# SparkFun_Teensy_Adapter.net
KiCad netlist of a schematic drawn in EAGLE
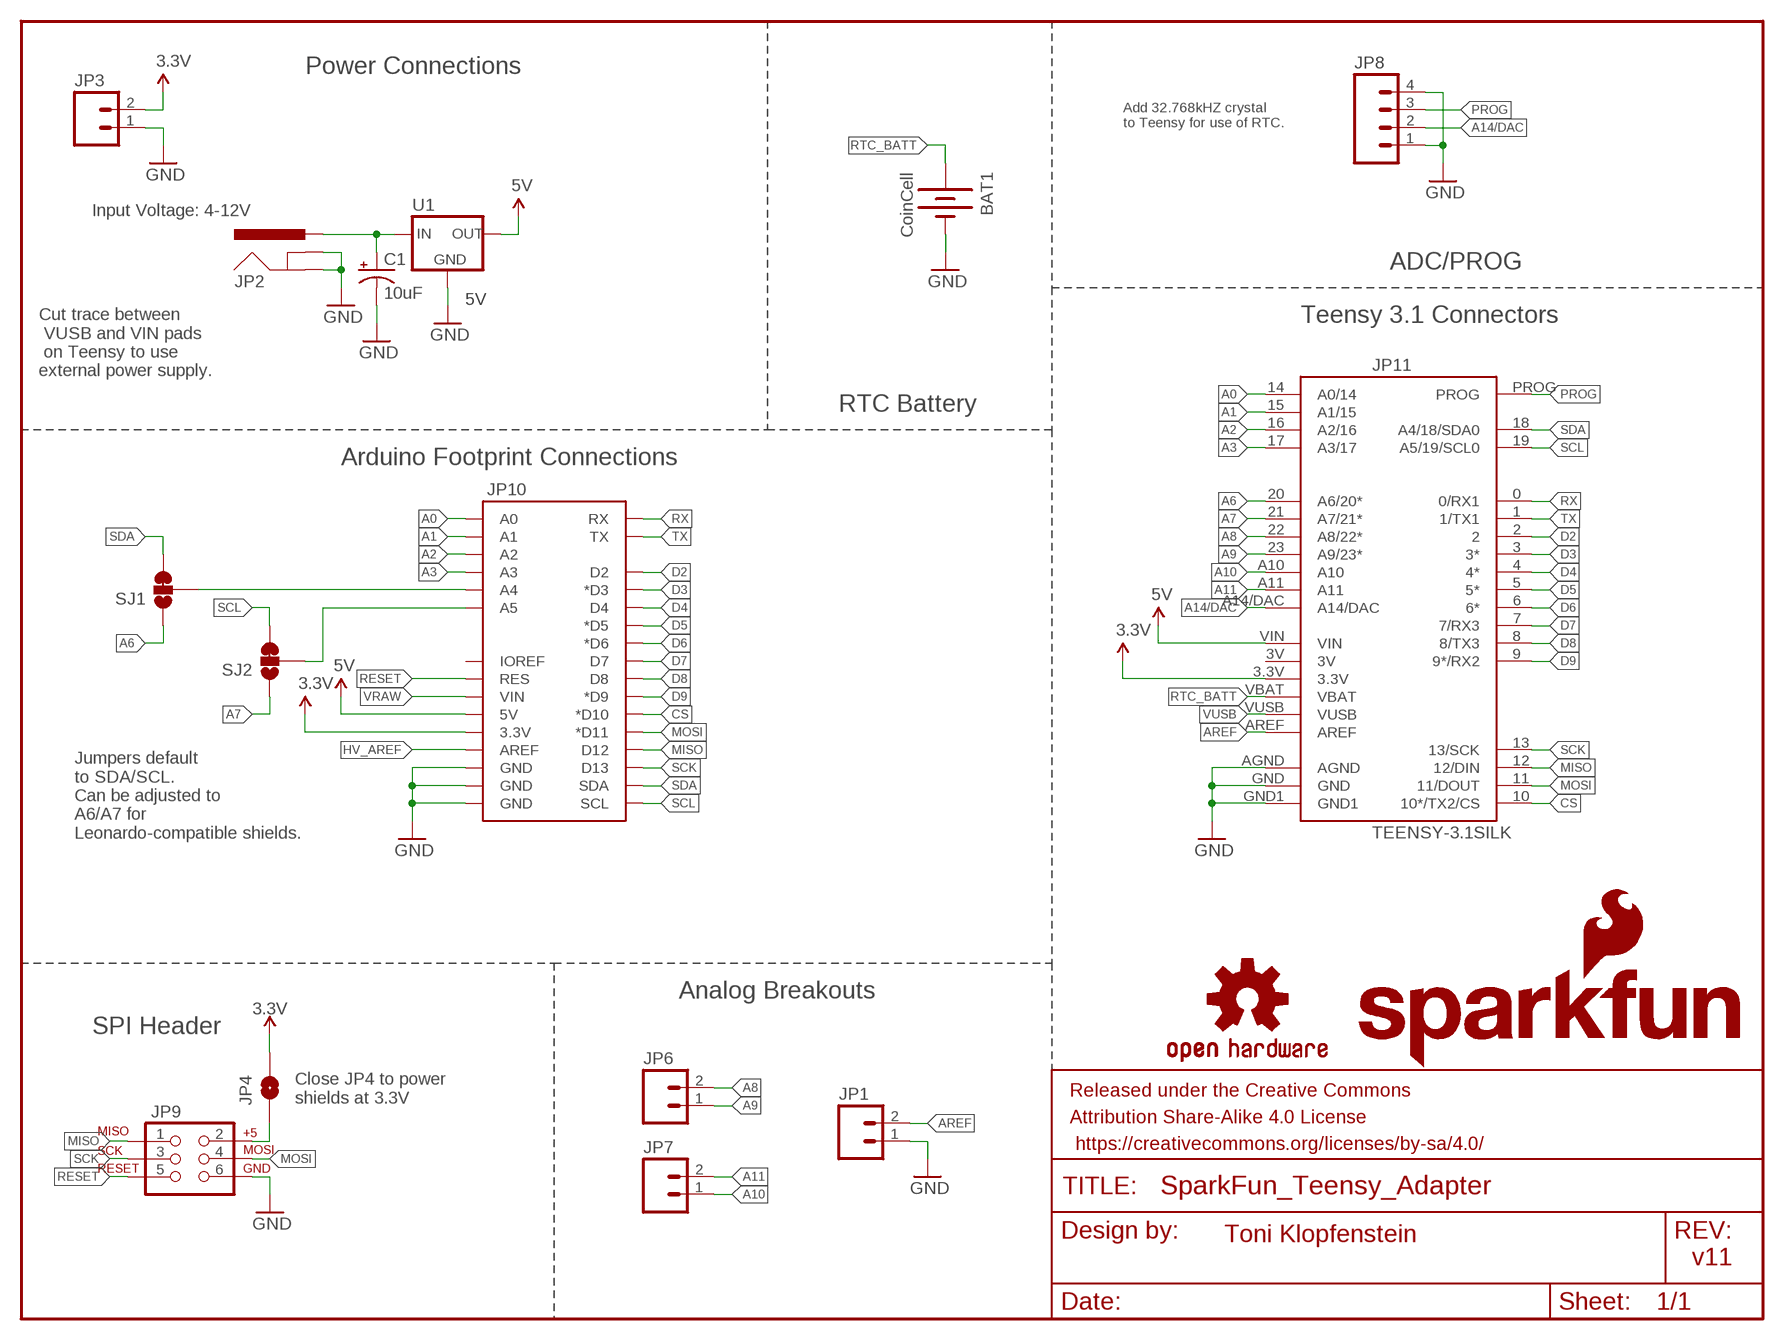
[diagram p0: schematic, sheet 1]

(export (version "E")
  (design (tool "Eeschema 10.0.6"))
  (components
    (comp (ref "BAT1")
      (value "CoinCell")
      (footprint "eagle-import:BATTCON_12MM_PTH")
      (libsource (lib "eagle-import") (part "BATTERY12PTH"))
    )
    (comp (ref "C1")
      (value "10uF")
      (footprint "eagle-import:CPOL-RADIAL-10UF-25V")
      (libsource (lib "eagle-import") (part "10UF-25V-20%(PTH)"))
    )
    (comp (ref "FRAME1")
      (value "FRAME-LETTER")
      (footprint "eagle-import:CREATIVE_COMMONS")
      (libsource (lib "eagle-import") (part "FRAME-LETTER"))
    )
    (comp (ref "JP1")
      (value "M02PTH")
      (footprint "eagle-import:1X02")
      (libsource (lib "eagle-import") (part "M02PTH"))
    )
    (comp (ref "JP2")
      (value "POWER_JACKPTH_LOCK")
      (footprint "eagle-import:POWER_JACK_PTH_LOCK")
      (libsource (lib "eagle-import") (part "POWER_JACKPTH_LOCK"))
    )
    (comp (ref "JP3")
      (value "JST2")
      (footprint "eagle-import:JST-2-PTH")
      (libsource (lib "eagle-import") (part "M02JST-PTH-2"))
    )
    (comp (ref "JP4")
      (value "JUMPER-SMT_2_NO_SILK")
      (footprint "eagle-import:SMT-JUMPER_2_NO_SILK")
      (libsource (lib "eagle-import") (part "JUMPER-SMT_2_NO_SILK"))
    )
    (comp (ref "JP6")
      (value "M02PTH")
      (footprint "eagle-import:1X02")
      (libsource (lib "eagle-import") (part "M02PTH"))
    )
    (comp (ref "JP7")
      (value "M02PTH")
      (footprint "eagle-import:1X02")
      (libsource (lib "eagle-import") (part "M02PTH"))
    )
    (comp (ref "JP8")
      (value "M04PTH")
      (footprint "eagle-import:1X04")
      (libsource (lib "eagle-import") (part "M04PTH"))
    )
    (comp (ref "JP9")
      (value "AVR_SPI_PRG_6PTH")
      (footprint "eagle-import:2X3")
      (libsource (lib "eagle-import") (part "AVR_SPI_PRG_6PTH"))
    )
    (comp (ref "JP10")
      (value "ARDUINO_R3_SHIELDUNO_R3_SHIELD_HOLES")
      (footprint "eagle-import:UNO_R3_SHIELD_HOLES")
      (libsource (lib "eagle-import") (part "ARDUINO_R3_SHIELDUNO_R3_SHIELD_HOLES"))
    )
    (comp (ref "JP11")
      (value "TEENSY-3.1SILK")
      (footprint "eagle-import:TEENSY-3.1")
      (libsource (lib "eagle-import") (part "TEENSY-3.1SILK"))
    )
    (comp (ref "LOGO1")
      (value "SFE_LOGO_NAME_FLAME.1_INCH")
      (footprint "eagle-import:SFE_LOGO_NAME_FLAME_.1")
      (libsource (lib "eagle-import") (part "SFE_LOGO_NAME_FLAME.1_INCH"))
    )
    (comp (ref "LOGO2")
      (value "OSHW-LOGOM")
      (footprint "eagle-import:OSHW-LOGO-M")
      (libsource (lib "eagle-import") (part "OSHW-LOGOM"))
    )
    (comp (ref "SJ1")
      (value "JUMPER-PAD-3-2OF3_NC_BY_TRACE_SMALL")
      (footprint "eagle-import:PAD-JUMPER-3-2OF3_NC_BY_TRACE_YES_SILK_FULL_BOX")
      (libsource (lib "eagle-import") (part "JUMPER-PAD-3-2OF3_NC_BY_TRACE_SMALL"))
    )
    (comp (ref "SJ2")
      (value "JUMPER-PAD-3-2OF3_NC_BY_TRACE_SMALL")
      (footprint "eagle-import:PAD-JUMPER-3-2OF3_NC_BY_TRACE_YES_SILK_FULL_BOX")
      (libsource (lib "eagle-import") (part "JUMPER-PAD-3-2OF3_NC_BY_TRACE_SMALL"))
    )
    (comp (ref "U1")
      (value "5V")
      (footprint "eagle-import:TO-220-ALT")
      (libsource (lib "eagle-import") (part "V_REG_78XX-TO-220"))
    )
  )
  (nets
    (net (code "1") (name "3.3V") (class "Default")
      (node (ref "JP10") (pin "3.3V") (pinfunction "3.3V_3.3V") (pintype "bidirectional"))
      (node (ref "JP11") (pin "3.3V") (pinfunction "3.3V_3.3V") (pintype "bidirectional"))
      (node (ref "JP3") (pin "2") (pinfunction "2_2") (pintype "passive"))
      (node (ref "JP4") (pin "2") (pinfunction "2_2") (pintype "passive"))
    )
    (net (code "2") (name "5V") (class "Default")
      (node (ref "JP10") (pin "5V") (pinfunction "5V_5V") (pintype "bidirectional"))
      (node (ref "JP11") (pin "VIN") (pinfunction "VIN_VIN") (pintype "bidirectional"))
      (node (ref "U1") (pin "OUT") (pinfunction "OUT_OUT") (pintype "output"))
    )
    (net (code "3") (name "A0") (class "Default")
      (node (ref "JP10") (pin "A0") (pinfunction "A0_A0") (pintype "bidirectional"))
      (node (ref "JP11") (pin "14") (pinfunction "A0/14_14") (pintype "bidirectional"))
    )
    (net (code "4") (name "A1") (class "Default")
      (node (ref "JP10") (pin "A1") (pinfunction "A1_A1") (pintype "bidirectional"))
      (node (ref "JP11") (pin "15") (pinfunction "A1/15_15") (pintype "bidirectional"))
    )
    (net (code "5") (name "A2") (class "Default")
      (node (ref "JP10") (pin "A2") (pinfunction "A2_A2") (pintype "bidirectional"))
      (node (ref "JP11") (pin "16") (pinfunction "A2/16_16") (pintype "bidirectional"))
    )
    (net (code "6") (name "A3") (class "Default")
      (node (ref "JP10") (pin "A3") (pinfunction "A3_A3") (pintype "bidirectional"))
      (node (ref "JP11") (pin "17") (pinfunction "A3/17_17") (pintype "bidirectional"))
    )
    (net (code "7") (name "A6") (class "Default")
      (node (ref "JP11") (pin "20") (pinfunction "A6/20*_20") (pintype "bidirectional"))
      (node (ref "SJ1") (pin "1") (pinfunction "1_1") (pintype "passive"))
    )
    (net (code "8") (name "A7") (class "Default")
      (node (ref "JP11") (pin "21") (pinfunction "A7/21*_21") (pintype "bidirectional"))
      (node (ref "SJ2") (pin "1") (pinfunction "1_1") (pintype "passive"))
    )
    (net (code "9") (name "A8") (class "Default")
      (node (ref "JP11") (pin "22") (pinfunction "A8/22*_22") (pintype "bidirectional"))
      (node (ref "JP6") (pin "2") (pinfunction "2_2") (pintype "passive"))
    )
    (net (code "10") (name "A9") (class "Default")
      (node (ref "JP11") (pin "23") (pinfunction "A9/23*_23") (pintype "bidirectional"))
      (node (ref "JP6") (pin "1") (pinfunction "1_1") (pintype "passive"))
    )
    (net (code "11") (name "A10") (class "Default")
      (node (ref "JP11") (pin "A10") (pinfunction "A10_A10") (pintype "bidirectional"))
      (node (ref "JP7") (pin "1") (pinfunction "1_1") (pintype "passive"))
    )
    (net (code "12") (name "A11") (class "Default")
      (node (ref "JP11") (pin "A11") (pinfunction "A11_A11") (pintype "bidirectional"))
      (node (ref "JP7") (pin "2") (pinfunction "2_2") (pintype "passive"))
    )
    (net (code "13") (name "A14{slash}DAC") (class "Default")
      (node (ref "JP11") (pin "A14/DAC") (pinfunction "A14/DAC_A14/DAC") (pintype "bidirectional"))
      (node (ref "JP8") (pin "2") (pinfunction "2_2") (pintype "passive"))
    )
    (net (code "14") (name "AREF") (class "Default")
      (node (ref "JP1") (pin "2") (pinfunction "2_2") (pintype "passive"))
      (node (ref "JP11") (pin "AREF") (pinfunction "AREF_AREF") (pintype "bidirectional"))
    )
    (net (code "15") (name "CS") (class "Default")
      (node (ref "JP10") (pin "D10") (pinfunction "*D10_D10") (pintype "bidirectional"))
      (node (ref "JP11") (pin "10") (pinfunction "10*/TX2/CS_10") (pintype "bidirectional"))
    )
    (net (code "16") (name "D2") (class "Default")
      (node (ref "JP10") (pin "D2") (pinfunction "D2_D2") (pintype "bidirectional"))
      (node (ref "JP11") (pin "2") (pinfunction "2_2") (pintype "bidirectional"))
    )
    (net (code "17") (name "D3") (class "Default")
      (node (ref "JP10") (pin "D3") (pinfunction "*D3_D3") (pintype "bidirectional"))
      (node (ref "JP11") (pin "3") (pinfunction "3*_3") (pintype "bidirectional"))
    )
    (net (code "18") (name "D4") (class "Default")
      (node (ref "JP10") (pin "D4") (pinfunction "D4_D4") (pintype "bidirectional"))
      (node (ref "JP11") (pin "4") (pinfunction "4*_4") (pintype "bidirectional"))
    )
    (net (code "19") (name "D5") (class "Default")
      (node (ref "JP10") (pin "D5") (pinfunction "*D5_D5") (pintype "bidirectional"))
      (node (ref "JP11") (pin "5") (pinfunction "5*_5") (pintype "bidirectional"))
    )
    (net (code "20") (name "D6") (class "Default")
      (node (ref "JP10") (pin "D6") (pinfunction "*D6_D6") (pintype "bidirectional"))
      (node (ref "JP11") (pin "6") (pinfunction "6*_6") (pintype "bidirectional"))
    )
    (net (code "21") (name "D7") (class "Default")
      (node (ref "JP10") (pin "D7") (pinfunction "D7_D7") (pintype "bidirectional"))
      (node (ref "JP11") (pin "7") (pinfunction "7/RX3_7") (pintype "bidirectional"))
    )
    (net (code "22") (name "D8") (class "Default")
      (node (ref "JP10") (pin "D8") (pinfunction "D8_D8") (pintype "bidirectional"))
      (node (ref "JP11") (pin "8") (pinfunction "8/TX3_8") (pintype "bidirectional"))
    )
    (net (code "23") (name "D9") (class "Default")
      (node (ref "JP10") (pin "D9") (pinfunction "*D9_D9") (pintype "bidirectional"))
      (node (ref "JP11") (pin "9") (pinfunction "9*/RX2_9") (pintype "bidirectional"))
    )
    (net (code "24") (name "GND") (class "Default")
      (node (ref "BAT1") (pin "GND") (pinfunction "-_GND") (pintype "power_in"))
      (node (ref "C1") (pin "2") (pinfunction "-_2") (pintype "passive"))
      (node (ref "JP1") (pin "1") (pinfunction "1_1") (pintype "passive"))
      (node (ref "JP10") (pin "GND@0") (pinfunction "GND_GND@0") (pintype "bidirectional"))
      (node (ref "JP10") (pin "GND@1") (pinfunction "GND_GND@1") (pintype "bidirectional"))
      (node (ref "JP10") (pin "GND@2") (pinfunction "GND_GND@2") (pintype "bidirectional"))
      (node (ref "JP11") (pin "AGND") (pinfunction "AGND_AGND") (pintype "bidirectional"))
      (node (ref "JP11") (pin "GND") (pinfunction "GND_GND") (pintype "bidirectional"))
      (node (ref "JP11") (pin "GND1") (pinfunction "GND1_GND1") (pintype "bidirectional"))
      (node (ref "JP2") (pin "GND") (pinfunction "GND_GND") (pintype "bidirectional"))
      (node (ref "JP2") (pin "GNDBREAK") (pinfunction "GNDBREAK_GNDBREAK") (pintype "bidirectional"))
      (node (ref "JP3") (pin "1") (pinfunction "1_1") (pintype "passive"))
      (node (ref "JP8") (pin "1") (pinfunction "1_1") (pintype "passive"))
      (node (ref "JP8") (pin "4") (pinfunction "4_4") (pintype "passive"))
      (node (ref "JP9") (pin "6") (pinfunction "6_6") (pintype "passive"))
      (node (ref "U1") (pin "GND") (pinfunction "GND_GND") (pintype "input"))
    )
    (net (code "25") (name "HV_AREF") (class "Default")
      (node (ref "JP10") (pin "AREF") (pinfunction "AREF_AREF") (pintype "bidirectional"))
    )
    (net (code "26") (name "MISO") (class "Default")
      (node (ref "JP10") (pin "D12") (pinfunction "D12_D12") (pintype "bidirectional"))
      (node (ref "JP11") (pin "12") (pinfunction "12/DIN_12") (pintype "bidirectional"))
      (node (ref "JP9") (pin "1") (pinfunction "1_1") (pintype "passive"))
    )
    (net (code "27") (name "MOSI") (class "Default")
      (node (ref "JP10") (pin "D11") (pinfunction "*D11_D11") (pintype "bidirectional"))
      (node (ref "JP11") (pin "11") (pinfunction "11/DOUT_11") (pintype "bidirectional"))
      (node (ref "JP9") (pin "4") (pinfunction "4_4") (pintype "passive"))
    )
    (net (code "28") (name "Net-(JP4-Pad1)") (class "Default")
      (node (ref "JP4") (pin "1") (pinfunction "1_1") (pintype "passive"))
      (node (ref "JP9") (pin "2") (pinfunction "2_2") (pintype "passive"))
    )
    (net (code "29") (name "Net-(JP10-PadA4)") (class "Default")
      (node (ref "JP10") (pin "A4") (pinfunction "A4_A4") (pintype "bidirectional"))
      (node (ref "SJ1") (pin "2") (pinfunction "2_2") (pintype "passive"))
    )
    (net (code "30") (name "Net-(JP10-PadA5)") (class "Default")
      (node (ref "JP10") (pin "A5") (pinfunction "A5_A5") (pintype "bidirectional"))
      (node (ref "SJ2") (pin "2") (pinfunction "2_2") (pintype "passive"))
    )
    (net (code "31") (name "PROG") (class "Default")
      (node (ref "JP11") (pin "PROG") (pinfunction "PROG_PROG") (pintype "bidirectional"))
      (node (ref "JP8") (pin "3") (pinfunction "3_3") (pintype "passive"))
    )
    (net (code "32") (name "RESET") (class "Default")
      (node (ref "JP10") (pin "RES") (pinfunction "RES_RES") (pintype "bidirectional"))
      (node (ref "JP9") (pin "5") (pinfunction "5_5") (pintype "passive"))
    )
    (net (code "33") (name "RTC_BATT") (class "Default")
      (node (ref "BAT1") (pin "VCC@1") (pinfunction "+_VCC@1") (pintype "power_in"))
      (node (ref "JP11") (pin "VBAT") (pinfunction "VBAT_VBAT") (pintype "bidirectional"))
    )
    (net (code "34") (name "RX") (class "Default")
      (node (ref "JP10") (pin "RX") (pinfunction "RX_RX") (pintype "bidirectional"))
      (node (ref "JP11") (pin "0") (pinfunction "0/RX1_0") (pintype "bidirectional"))
    )
    (net (code "35") (name "SCK") (class "Default")
      (node (ref "JP10") (pin "D13") (pinfunction "D13_D13") (pintype "bidirectional"))
      (node (ref "JP11") (pin "13") (pinfunction "13/SCK_13") (pintype "bidirectional"))
      (node (ref "JP9") (pin "3") (pinfunction "3_3") (pintype "passive"))
    )
    (net (code "36") (name "SCL") (class "Default")
      (node (ref "JP10") (pin "SCL") (pinfunction "SCL_SCL") (pintype "bidirectional"))
      (node (ref "JP11") (pin "19") (pinfunction "A5/19/SCL0_19") (pintype "bidirectional"))
      (node (ref "SJ2") (pin "3") (pinfunction "3_3") (pintype "passive"))
    )
    (net (code "37") (name "SDA") (class "Default")
      (node (ref "JP10") (pin "SDA") (pinfunction "SDA_SDA") (pintype "bidirectional"))
      (node (ref "JP11") (pin "18") (pinfunction "A4/18/SDA0_18") (pintype "bidirectional"))
      (node (ref "SJ1") (pin "3") (pinfunction "3_3") (pintype "passive"))
    )
    (net (code "38") (name "TX") (class "Default")
      (node (ref "JP10") (pin "TX") (pinfunction "TX_TX") (pintype "bidirectional"))
      (node (ref "JP11") (pin "1") (pinfunction "1/TX1_1") (pintype "bidirectional"))
    )
    (net (code "39") (name "VRAW") (class "Default")
      (node (ref "C1") (pin "1") (pinfunction "+_1") (pintype "passive"))
      (node (ref "JP10") (pin "VIN") (pinfunction "VIN_VIN") (pintype "bidirectional"))
      (node (ref "JP2") (pin "PWR") (pinfunction "PWR_PWR") (pintype "bidirectional"))
      (node (ref "U1") (pin "IN") (pinfunction "IN_IN") (pintype "input"))
    )
    (net (code "40") (name "VUSB") (class "Default")
      (node (ref "JP11") (pin "VUSB") (pinfunction "VUSB_VUSB") (pintype "bidirectional"))
    )
    (net (code "41") (name "unconnected-(JP10-PadIOREF)") (class "Default")
      (node (ref "JP10") (pin "IOREF") (pinfunction "IOREF_IOREF") (pintype "bidirectional"))
    )
    (net (code "42") (name "unconnected-(JP11-Pad3V)") (class "Default")
      (node (ref "JP11") (pin "3V") (pinfunction "3V_3V") (pintype "bidirectional"))
    )
  )
)
